# ad597_breakout_v1.net
KiCad netlist of a schematic drawn in EAGLE
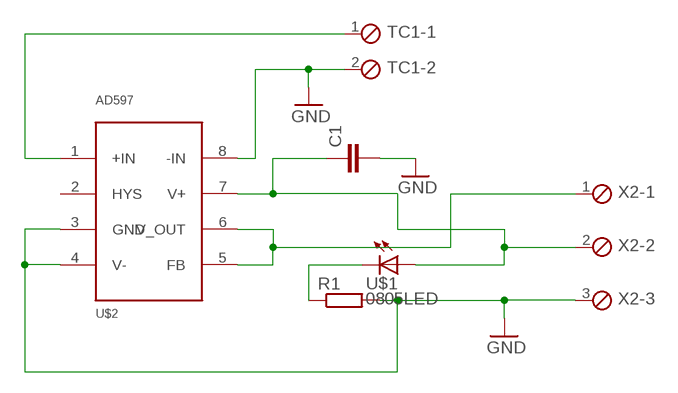
[diagram p0: schematic, sheet 1]

(export (version "E")
  (design (tool "Eeschema 10.0.6"))
  (components
    (comp (ref "C1")
      (value "C-EUC0805")
      (footprint "eagle-import:C0805")
      (libsource (lib "eagle-import") (part "C-EUC0805"))
    )
    (comp (ref "R1")
      (value "R-EU_R0805")
      (footprint "eagle-import:R0805")
      (libsource (lib "eagle-import") (part "R-EU_R0805"))
    )
    (comp (ref "TC1")
      (value "MPT2")
      (footprint "eagle-import:2POL254")
      (libsource (lib "eagle-import") (part "MPT2"))
    )
    (comp (ref "U$1")
      (value "0805LED")
      (footprint "eagle-import:0805LED")
      (libsource (lib "eagle-import") (part "0805LED"))
    )
    (comp (ref "U$2")
      (value "AD597")
      (footprint "eagle-import:SOP8")
      (libsource (lib "eagle-import") (part "AD597"))
    )
    (comp (ref "X2")
      (value "MPT3")
      (footprint "eagle-import:3POL254")
      (libsource (lib "eagle-import") (part "MPT3"))
    )
  )
  (nets
    (net (code "1") (name "GND") (class "Default")
      (node (ref "C1") (pin "2") (pinfunction "2_2") (pintype "passive"))
      (node (ref "R1") (pin "2") (pinfunction "2_2") (pintype "passive"))
      (node (ref "TC1") (pin "2") (pinfunction "1_2") (pintype "passive"))
      (node (ref "U$2") (pin "3") (pinfunction "GND_3") (pintype "bidirectional"))
      (node (ref "U$2") (pin "4") (pinfunction "V-_4") (pintype "bidirectional"))
      (node (ref "U$2") (pin "8") (pinfunction "-IN_8") (pintype "bidirectional"))
      (node (ref "X2") (pin "3") (pinfunction "1_3") (pintype "passive"))
    )
    (net (code "2") (name "Net-(R1-Pad1)") (class "Default")
      (node (ref "R1") (pin "1") (pinfunction "1_1") (pintype "passive"))
      (node (ref "U$1") (pin "C") (pinfunction "C_C") (pintype "passive"))
    )
    (net (code "3") (name "Net-(U$2-+IN)") (class "Default")
      (node (ref "TC1") (pin "1") (pinfunction "1_1") (pintype "passive"))
      (node (ref "U$2") (pin "1") (pinfunction "+IN_1") (pintype "bidirectional"))
    )
    (net (code "4") (name "Net-(U$2-FB)") (class "Default")
      (node (ref "U$2") (pin "5") (pinfunction "FB_5") (pintype "bidirectional"))
      (node (ref "U$2") (pin "6") (pinfunction "V_OUT_6") (pintype "bidirectional"))
      (node (ref "X2") (pin "1") (pinfunction "1_1") (pintype "passive"))
    )
    (net (code "5") (name "Net-(U$2-V+)") (class "Default")
      (node (ref "C1") (pin "1") (pinfunction "1_1") (pintype "passive"))
      (node (ref "U$1") (pin "A") (pinfunction "A_A") (pintype "passive"))
      (node (ref "U$2") (pin "7") (pinfunction "V+_7") (pintype "bidirectional"))
      (node (ref "X2") (pin "2") (pinfunction "1_2") (pintype "passive"))
    )
    (net (code "6") (name "unconnected-(U$2-HYS-Pad2)") (class "Default")
      (node (ref "U$2") (pin "2") (pinfunction "HYS_2") (pintype "bidirectional"))
    )
  )
)
